# rgb-vfd-matrix.net
KiCad netlist of a schematic drawn in EAGLE
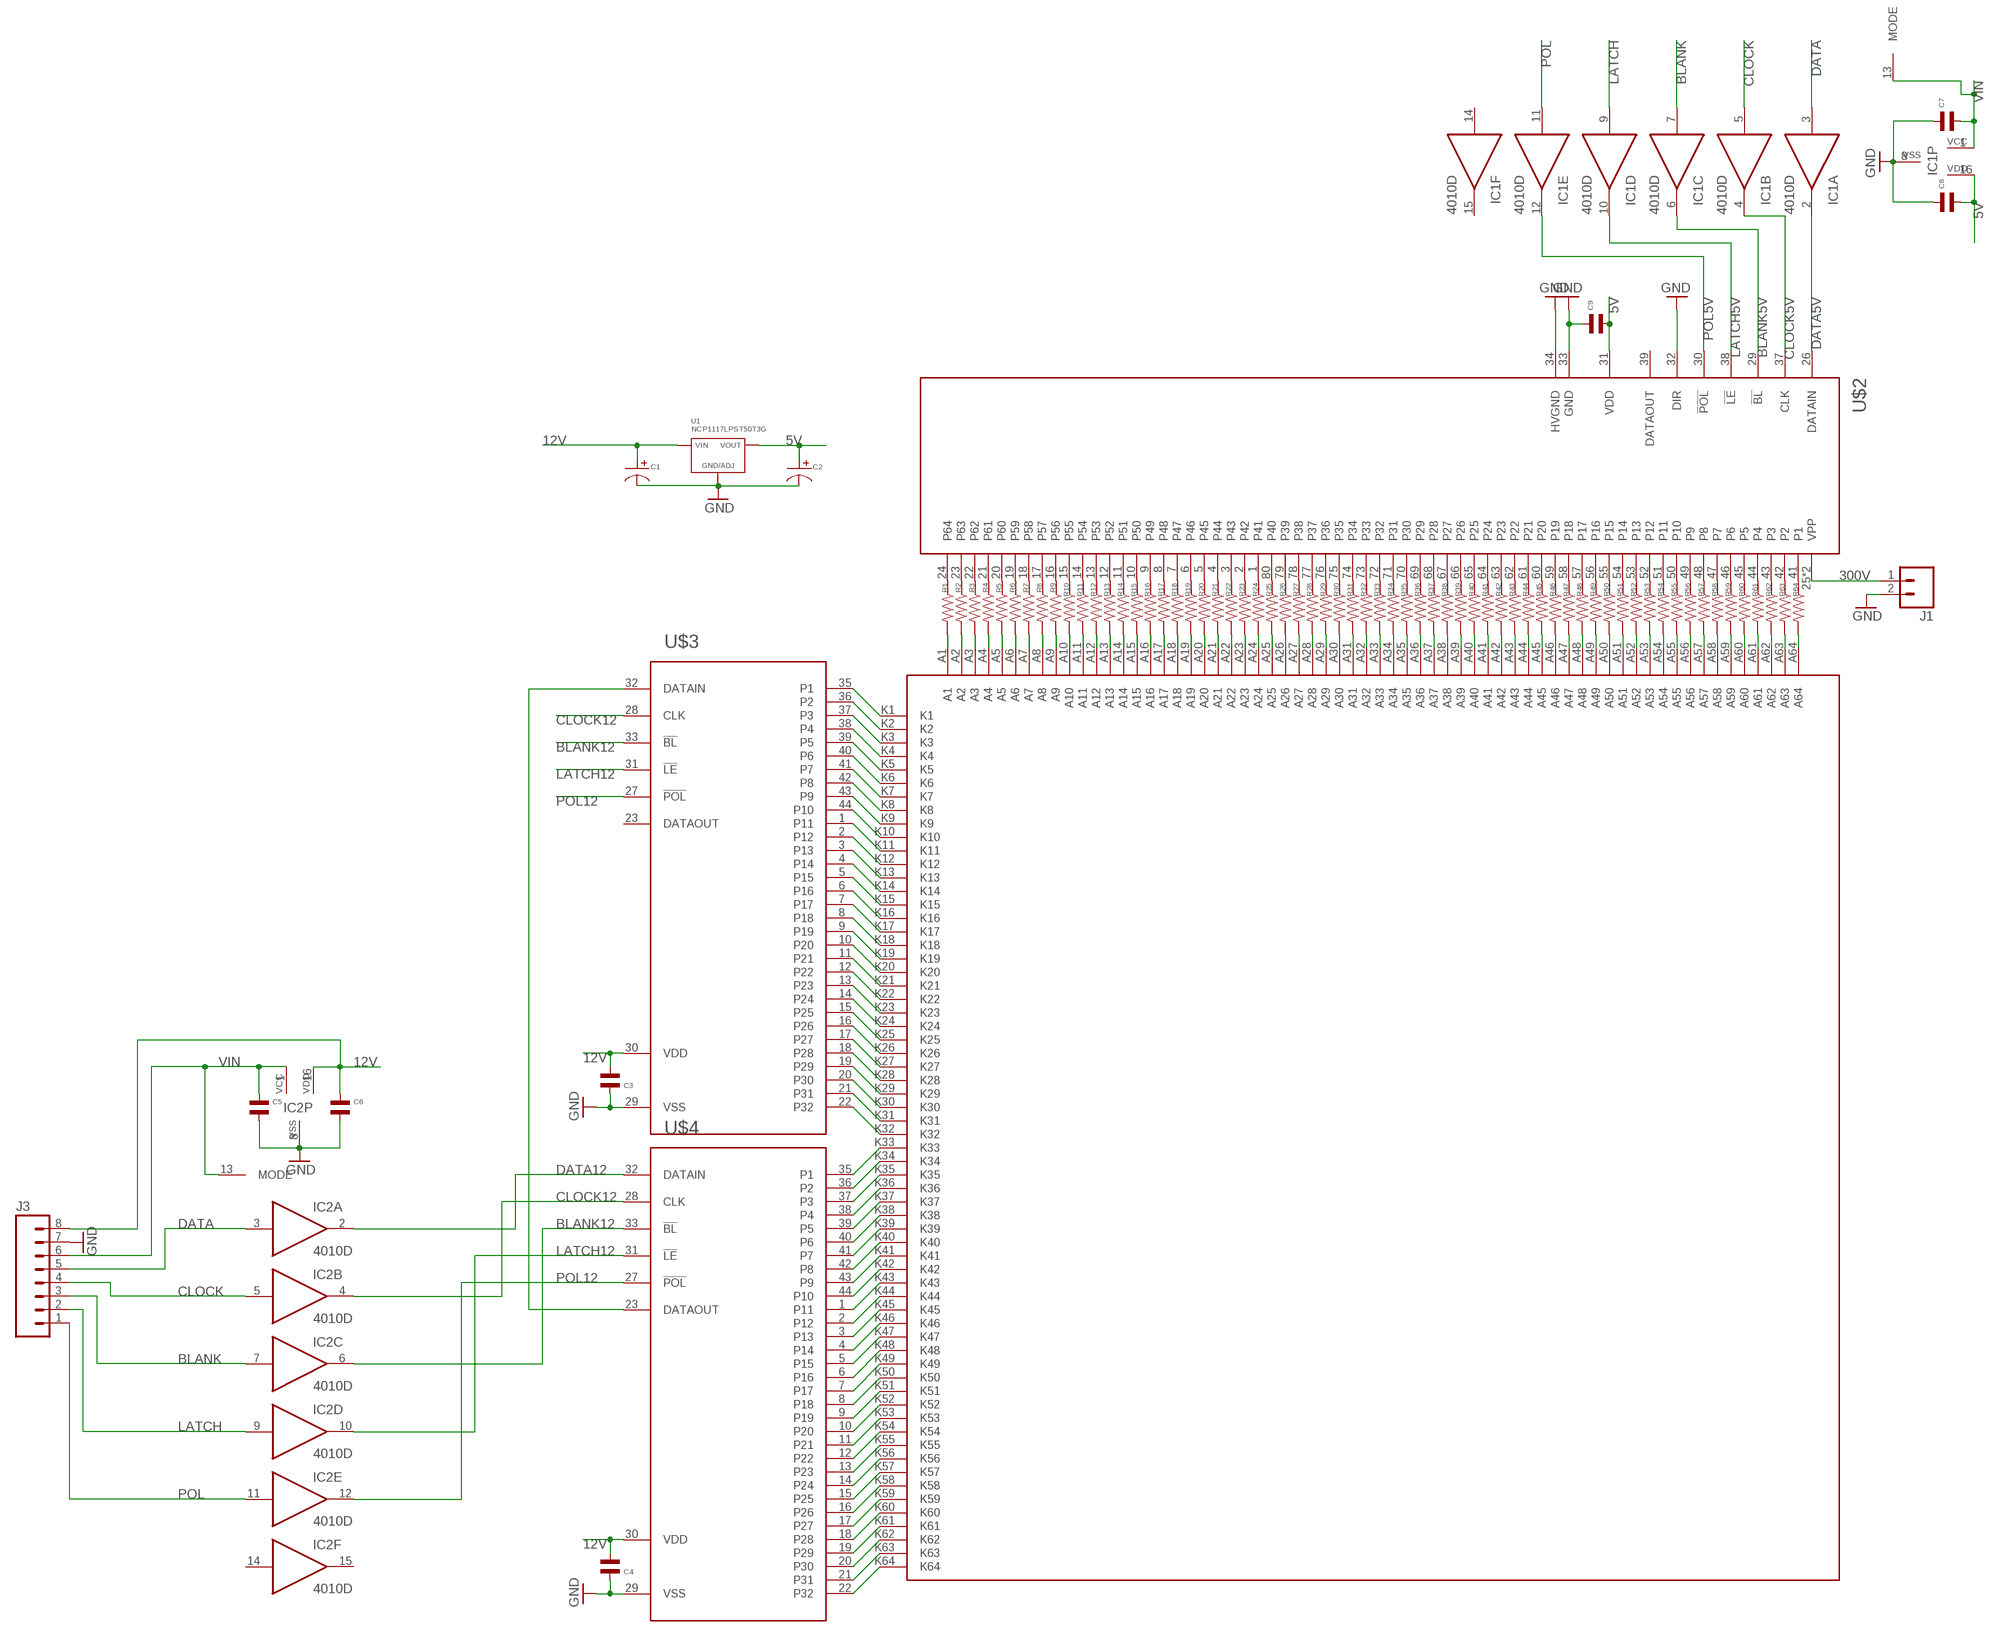
[diagram p0: schematic, sheet 1]

(export (version "E")
  (design (tool "Eeschema 10.0.6"))
  (components
    (comp (ref "C1")
      (value "CAPACITOR_P_8MM")
      (footprint "eagle-import:CP8MM")
      (libsource (lib "eagle-import") (part "CAPACITOR_P_8MM"))
    )
    (comp (ref "C2")
      (value "CAPACITOR_P_8MM")
      (footprint "eagle-import:CP8MM")
      (libsource (lib "eagle-import") (part "CAPACITOR_P_8MM"))
    )
    (comp (ref "C3")
      (value "CAPACITOR_NP_0603")
      (footprint "eagle-import:C0603")
      (libsource (lib "eagle-import") (part "CAPACITOR_NP_0603"))
    )
    (comp (ref "C4")
      (value "CAPACITOR_NP_0603")
      (footprint "eagle-import:C0603")
      (libsource (lib "eagle-import") (part "CAPACITOR_NP_0603"))
    )
    (comp (ref "C5")
      (value "CAPACITOR_NP_0603")
      (footprint "eagle-import:C0603")
      (libsource (lib "eagle-import") (part "CAPACITOR_NP_0603"))
    )
    (comp (ref "C6")
      (value "CAPACITOR_NP_0603")
      (footprint "eagle-import:C0603")
      (libsource (lib "eagle-import") (part "CAPACITOR_NP_0603"))
    )
    (comp (ref "C7")
      (value "CAPACITOR_NP_0603")
      (footprint "eagle-import:C0603")
      (libsource (lib "eagle-import") (part "CAPACITOR_NP_0603"))
    )
    (comp (ref "C8")
      (value "CAPACITOR_NP_0603")
      (footprint "eagle-import:C0603")
      (libsource (lib "eagle-import") (part "CAPACITOR_NP_0603"))
    )
    (comp (ref "C9")
      (value "CAPACITOR_NP_0603")
      (footprint "eagle-import:C0603")
      (libsource (lib "eagle-import") (part "CAPACITOR_NP_0603"))
    )
    (comp (ref "IC1")
      (value "4010D")
      (footprint "eagle-import:SO16")
      (libsource (lib "eagle-import") (part "4010D"))
    )
    (comp (ref "IC2")
      (value "4010D")
      (footprint "eagle-import:SO16")
      (libsource (lib "eagle-import") (part "4010D"))
    )
    (comp (ref "J1")
      (value "M023.5MM")
      (footprint "eagle-import:SCREWTERMINAL-3.5MM-2")
      (libsource (lib "eagle-import") (part "M023.5MM"))
    )
    (comp (ref "J3")
      (value "M083.5MM-8")
      (footprint "eagle-import:SCREWTERMINAL-3.5MM-8")
      (libsource (lib "eagle-import") (part "M083.5MM-8"))
    )
    (comp (ref "R1")
      (value "RESISTOR_0805")
      (footprint "eagle-import:R0805")
      (libsource (lib "eagle-import") (part "RESISTOR_0805"))
    )
    (comp (ref "R2")
      (value "RESISTOR_0805")
      (footprint "eagle-import:R0805")
      (libsource (lib "eagle-import") (part "RESISTOR_0805"))
    )
    (comp (ref "R3")
      (value "RESISTOR_0805")
      (footprint "eagle-import:R0805")
      (libsource (lib "eagle-import") (part "RESISTOR_0805"))
    )
    (comp (ref "R4")
      (value "RESISTOR_0805")
      (footprint "eagle-import:R0805")
      (libsource (lib "eagle-import") (part "RESISTOR_0805"))
    )
    (comp (ref "R5")
      (value "RESISTOR_0805")
      (footprint "eagle-import:R0805")
      (libsource (lib "eagle-import") (part "RESISTOR_0805"))
    )
    (comp (ref "R6")
      (value "RESISTOR_0805")
      (footprint "eagle-import:R0805")
      (libsource (lib "eagle-import") (part "RESISTOR_0805"))
    )
    (comp (ref "R7")
      (value "RESISTOR_0805")
      (footprint "eagle-import:R0805")
      (libsource (lib "eagle-import") (part "RESISTOR_0805"))
    )
    (comp (ref "R8")
      (value "RESISTOR_0805")
      (footprint "eagle-import:R0805")
      (libsource (lib "eagle-import") (part "RESISTOR_0805"))
    )
    (comp (ref "R9")
      (value "RESISTOR_0805")
      (footprint "eagle-import:R0805")
      (libsource (lib "eagle-import") (part "RESISTOR_0805"))
    )
    (comp (ref "R10")
      (value "RESISTOR_0805")
      (footprint "eagle-import:R0805")
      (libsource (lib "eagle-import") (part "RESISTOR_0805"))
    )
    (comp (ref "R11")
      (value "RESISTOR_0805")
      (footprint "eagle-import:R0805")
      (libsource (lib "eagle-import") (part "RESISTOR_0805"))
    )
    (comp (ref "R12")
      (value "RESISTOR_0805")
      (footprint "eagle-import:R0805")
      (libsource (lib "eagle-import") (part "RESISTOR_0805"))
    )
    (comp (ref "R13")
      (value "RESISTOR_0805")
      (footprint "eagle-import:R0805")
      (libsource (lib "eagle-import") (part "RESISTOR_0805"))
    )
    (comp (ref "R14")
      (value "RESISTOR_0805")
      (footprint "eagle-import:R0805")
      (libsource (lib "eagle-import") (part "RESISTOR_0805"))
    )
    (comp (ref "R15")
      (value "RESISTOR_0805")
      (footprint "eagle-import:R0805")
      (libsource (lib "eagle-import") (part "RESISTOR_0805"))
    )
    (comp (ref "R16")
      (value "RESISTOR_0805")
      (footprint "eagle-import:R0805")
      (libsource (lib "eagle-import") (part "RESISTOR_0805"))
    )
    (comp (ref "R17")
      (value "RESISTOR_0805")
      (footprint "eagle-import:R0805")
      (libsource (lib "eagle-import") (part "RESISTOR_0805"))
    )
    (comp (ref "R18")
      (value "RESISTOR_0805")
      (footprint "eagle-import:R0805")
      (libsource (lib "eagle-import") (part "RESISTOR_0805"))
    )
    (comp (ref "R19")
      (value "RESISTOR_0805")
      (footprint "eagle-import:R0805")
      (libsource (lib "eagle-import") (part "RESISTOR_0805"))
    )
    (comp (ref "R20")
      (value "RESISTOR_0805")
      (footprint "eagle-import:R0805")
      (libsource (lib "eagle-import") (part "RESISTOR_0805"))
    )
    (comp (ref "R21")
      (value "RESISTOR_0805")
      (footprint "eagle-import:R0805")
      (libsource (lib "eagle-import") (part "RESISTOR_0805"))
    )
    (comp (ref "R22")
      (value "RESISTOR_0805")
      (footprint "eagle-import:R0805")
      (libsource (lib "eagle-import") (part "RESISTOR_0805"))
    )
    (comp (ref "R23")
      (value "RESISTOR_0805")
      (footprint "eagle-import:R0805")
      (libsource (lib "eagle-import") (part "RESISTOR_0805"))
    )
    (comp (ref "R24")
      (value "RESISTOR_0805")
      (footprint "eagle-import:R0805")
      (libsource (lib "eagle-import") (part "RESISTOR_0805"))
    )
    (comp (ref "R25")
      (value "RESISTOR_0805")
      (footprint "eagle-import:R0805")
      (libsource (lib "eagle-import") (part "RESISTOR_0805"))
    )
    (comp (ref "R26")
      (value "RESISTOR_0805")
      (footprint "eagle-import:R0805")
      (libsource (lib "eagle-import") (part "RESISTOR_0805"))
    )
    (comp (ref "R27")
      (value "RESISTOR_0805")
      (footprint "eagle-import:R0805")
      (libsource (lib "eagle-import") (part "RESISTOR_0805"))
    )
    (comp (ref "R28")
      (value "RESISTOR_0805")
      (footprint "eagle-import:R0805")
      (libsource (lib "eagle-import") (part "RESISTOR_0805"))
    )
    (comp (ref "R29")
      (value "RESISTOR_0805")
      (footprint "eagle-import:R0805")
      (libsource (lib "eagle-import") (part "RESISTOR_0805"))
    )
    (comp (ref "R30")
      (value "RESISTOR_0805")
      (footprint "eagle-import:R0805")
      (libsource (lib "eagle-import") (part "RESISTOR_0805"))
    )
    (comp (ref "R31")
      (value "RESISTOR_0805")
      (footprint "eagle-import:R0805")
      (libsource (lib "eagle-import") (part "RESISTOR_0805"))
    )
    (comp (ref "R32")
      (value "RESISTOR_0805")
      (footprint "eagle-import:R0805")
      (libsource (lib "eagle-import") (part "RESISTOR_0805"))
    )
    (comp (ref "R33")
      (value "RESISTOR_0805")
      (footprint "eagle-import:R0805")
      (libsource (lib "eagle-import") (part "RESISTOR_0805"))
    )
    (comp (ref "R34")
      (value "RESISTOR_0805")
      (footprint "eagle-import:R0805")
      (libsource (lib "eagle-import") (part "RESISTOR_0805"))
    )
    (comp (ref "R35")
      (value "RESISTOR_0805")
      (footprint "eagle-import:R0805")
      (libsource (lib "eagle-import") (part "RESISTOR_0805"))
    )
    (comp (ref "R36")
      (value "RESISTOR_0805")
      (footprint "eagle-import:R0805")
      (libsource (lib "eagle-import") (part "RESISTOR_0805"))
    )
    (comp (ref "R37")
      (value "RESISTOR_0805")
      (footprint "eagle-import:R0805")
      (libsource (lib "eagle-import") (part "RESISTOR_0805"))
    )
    (comp (ref "R38")
      (value "RESISTOR_0805")
      (footprint "eagle-import:R0805")
      (libsource (lib "eagle-import") (part "RESISTOR_0805"))
    )
    (comp (ref "R39")
      (value "RESISTOR_0805")
      (footprint "eagle-import:R0805")
      (libsource (lib "eagle-import") (part "RESISTOR_0805"))
    )
    (comp (ref "R40")
      (value "RESISTOR_0805")
      (footprint "eagle-import:R0805")
      (libsource (lib "eagle-import") (part "RESISTOR_0805"))
    )
    (comp (ref "R41")
      (value "RESISTOR_0805")
      (footprint "eagle-import:R0805")
      (libsource (lib "eagle-import") (part "RESISTOR_0805"))
    )
    (comp (ref "R42")
      (value "RESISTOR_0805")
      (footprint "eagle-import:R0805")
      (libsource (lib "eagle-import") (part "RESISTOR_0805"))
    )
    (comp (ref "R43")
      (value "RESISTOR_0805")
      (footprint "eagle-import:R0805")
      (libsource (lib "eagle-import") (part "RESISTOR_0805"))
    )
    (comp (ref "R44")
      (value "RESISTOR_0805")
      (footprint "eagle-import:R0805")
      (libsource (lib "eagle-import") (part "RESISTOR_0805"))
    )
    (comp (ref "R45")
      (value "RESISTOR_0805")
      (footprint "eagle-import:R0805")
      (libsource (lib "eagle-import") (part "RESISTOR_0805"))
    )
    (comp (ref "R46")
      (value "RESISTOR_0805")
      (footprint "eagle-import:R0805")
      (libsource (lib "eagle-import") (part "RESISTOR_0805"))
    )
    (comp (ref "R47")
      (value "RESISTOR_0805")
      (footprint "eagle-import:R0805")
      (libsource (lib "eagle-import") (part "RESISTOR_0805"))
    )
    (comp (ref "R48")
      (value "RESISTOR_0805")
      (footprint "eagle-import:R0805")
      (libsource (lib "eagle-import") (part "RESISTOR_0805"))
    )
    (comp (ref "R49")
      (value "RESISTOR_0805")
      (footprint "eagle-import:R0805")
      (libsource (lib "eagle-import") (part "RESISTOR_0805"))
    )
    (comp (ref "R50")
      (value "RESISTOR_0805")
      (footprint "eagle-import:R0805")
      (libsource (lib "eagle-import") (part "RESISTOR_0805"))
    )
    (comp (ref "R51")
      (value "RESISTOR_0805")
      (footprint "eagle-import:R0805")
      (libsource (lib "eagle-import") (part "RESISTOR_0805"))
    )
    (comp (ref "R52")
      (value "RESISTOR_0805")
      (footprint "eagle-import:R0805")
      (libsource (lib "eagle-import") (part "RESISTOR_0805"))
    )
    (comp (ref "R53")
      (value "RESISTOR_0805")
      (footprint "eagle-import:R0805")
      (libsource (lib "eagle-import") (part "RESISTOR_0805"))
    )
    (comp (ref "R54")
      (value "RESISTOR_0805")
      (footprint "eagle-import:R0805")
      (libsource (lib "eagle-import") (part "RESISTOR_0805"))
    )
    (comp (ref "R55")
      (value "RESISTOR_0805")
      (footprint "eagle-import:R0805")
      (libsource (lib "eagle-import") (part "RESISTOR_0805"))
    )
    (comp (ref "R56")
      (value "RESISTOR_0805")
      (footprint "eagle-import:R0805")
      (libsource (lib "eagle-import") (part "RESISTOR_0805"))
    )
    (comp (ref "R57")
      (value "RESISTOR_0805")
      (footprint "eagle-import:R0805")
      (libsource (lib "eagle-import") (part "RESISTOR_0805"))
    )
    (comp (ref "R58")
      (value "RESISTOR_0805")
      (footprint "eagle-import:R0805")
      (libsource (lib "eagle-import") (part "RESISTOR_0805"))
    )
    (comp (ref "R59")
      (value "RESISTOR_0805")
      (footprint "eagle-import:R0805")
      (libsource (lib "eagle-import") (part "RESISTOR_0805"))
    )
    (comp (ref "R60")
      (value "RESISTOR_0805")
      (footprint "eagle-import:R0805")
      (libsource (lib "eagle-import") (part "RESISTOR_0805"))
    )
    (comp (ref "R61")
      (value "RESISTOR_0805")
      (footprint "eagle-import:R0805")
      (libsource (lib "eagle-import") (part "RESISTOR_0805"))
    )
    (comp (ref "R62")
      (value "RESISTOR_0805")
      (footprint "eagle-import:R0805")
      (libsource (lib "eagle-import") (part "RESISTOR_0805"))
    )
    (comp (ref "R63")
      (value "RESISTOR_0805")
      (footprint "eagle-import:R0805")
      (libsource (lib "eagle-import") (part "RESISTOR_0805"))
    )
    (comp (ref "R64")
      (value "RESISTOR_0805")
      (footprint "eagle-import:R0805")
      (libsource (lib "eagle-import") (part "RESISTOR_0805"))
    )
    (comp (ref "U$1")
      (value "RGBVFDMATRIX")
      (footprint "eagle-import:RGBVFDMATRIX")
      (libsource (lib "eagle-import") (part "RGBVFDMATRIX"))
    )
    (comp (ref "U$2")
      (value "HV507")
      (footprint "eagle-import:PQFP80")
      (libsource (lib "eagle-import") (part "HV507"))
    )
    (comp (ref "U$3")
      (value "HV5530")
      (footprint "eagle-import:PQFP44")
      (libsource (lib "eagle-import") (part "HV5530"))
    )
    (comp (ref "U$4")
      (value "HV5530")
      (footprint "eagle-import:PQFP44")
      (libsource (lib "eagle-import") (part "HV5530"))
    )
    (comp (ref "U1")
      (value "NCP1117LPST50T3G")
      (footprint "eagle-import:SOT-223-3")
      (fields (field (name "HOUSEPART") "NO"))
      (libsource (lib "eagle-import") (part "NCP1117LPST50T3G"))
    )
  )
  (nets
    (net (code "1") (name "/5V") (class "Default")
      (node (ref "C2") (pin "P$1") (pinfunction "P$1_P$1") (pintype "passive"))
      (node (ref "C8") (pin "P$2") (pinfunction "P$2_P$2") (pintype "passive"))
      (node (ref "C9") (pin "P$2") (pinfunction "P$2_P$2") (pintype "passive"))
      (node (ref "IC1") (pin "16") (pinfunction "VDD_16") (pintype "power_in"))
      (node (ref "U$2") (pin "31") (pinfunction "VDD_31") (pintype "bidirectional"))
      (node (ref "U1") (pin "P$1") (pinfunction "VOUT_P$1") (pintype "bidirectional"))
      (node (ref "U1") (pin "P$3") (pinfunction "VOUT_P$3") (pintype "bidirectional"))
    )
    (net (code "2") (name "/12V") (class "Default")
      (node (ref "C1") (pin "P$1") (pinfunction "P$1_P$1") (pintype "passive"))
      (node (ref "C3") (pin "P$2") (pinfunction "P$2_P$2") (pintype "passive"))
      (node (ref "C4") (pin "P$2") (pinfunction "P$2_P$2") (pintype "passive"))
      (node (ref "C6") (pin "P$1") (pinfunction "P$1_P$1") (pintype "passive"))
      (node (ref "IC2") (pin "16") (pinfunction "VDD_16") (pintype "power_in"))
      (node (ref "J3") (pin "8") (pinfunction "8_8") (pintype "passive"))
      (node (ref "U$3") (pin "30") (pinfunction "VDD_30") (pintype "bidirectional"))
      (node (ref "U$4") (pin "30") (pinfunction "VDD_30") (pintype "bidirectional"))
      (node (ref "U1") (pin "P$4") (pinfunction "VIN_P$4") (pintype "bidirectional"))
    )
    (net (code "3") (name "/300V") (class "Default")
      (node (ref "J1") (pin "1") (pinfunction "1_1") (pintype "passive"))
      (node (ref "U$2") (pin "25") (pinfunction "VPP_25") (pintype "bidirectional"))
      (node (ref "U$2") (pin "40") (pinfunction "VPP_40") (pintype "bidirectional"))
    )
    (net (code "4") (name "/BLANK") (class "Default")
      (node (ref "IC1") (pin "7") (pinfunction "I_7") (pintype "input"))
      (node (ref "IC2") (pin "7") (pinfunction "I_7") (pintype "input"))
      (node (ref "J3") (pin "3") (pinfunction "3_3") (pintype "passive"))
    )
    (net (code "5") (name "/BLANK5V") (class "Default")
      (node (ref "IC1") (pin "6") (pinfunction "O_6") (pintype "output"))
      (node (ref "U$2") (pin "29") (pinfunction "~{BL}_29") (pintype "bidirectional"))
    )
    (net (code "6") (name "/BLANK12") (class "Default")
      (node (ref "IC2") (pin "6") (pinfunction "O_6") (pintype "output"))
      (node (ref "U$3") (pin "33") (pinfunction "~{BL}_33") (pintype "bidirectional"))
      (node (ref "U$4") (pin "33") (pinfunction "~{BL}_33") (pintype "bidirectional"))
    )
    (net (code "7") (name "/CLOCK") (class "Default")
      (node (ref "IC1") (pin "5") (pinfunction "I_5") (pintype "input"))
      (node (ref "IC2") (pin "5") (pinfunction "I_5") (pintype "input"))
      (node (ref "J3") (pin "4") (pinfunction "4_4") (pintype "passive"))
    )
    (net (code "8") (name "/CLOCK5V") (class "Default")
      (node (ref "IC1") (pin "4") (pinfunction "O_4") (pintype "output"))
      (node (ref "U$2") (pin "37") (pinfunction "CLK_37") (pintype "bidirectional"))
    )
    (net (code "9") (name "/CLOCK12") (class "Default")
      (node (ref "IC2") (pin "4") (pinfunction "O_4") (pintype "output"))
      (node (ref "U$3") (pin "28") (pinfunction "CLK_28") (pintype "bidirectional"))
      (node (ref "U$4") (pin "28") (pinfunction "CLK_28") (pintype "bidirectional"))
    )
    (net (code "10") (name "/DATA") (class "Default")
      (node (ref "IC1") (pin "3") (pinfunction "I_3") (pintype "input"))
      (node (ref "IC2") (pin "3") (pinfunction "I_3") (pintype "input"))
      (node (ref "J3") (pin "5") (pinfunction "5_5") (pintype "passive"))
    )
    (net (code "11") (name "/DATA5V") (class "Default")
      (node (ref "IC1") (pin "2") (pinfunction "O_2") (pintype "output"))
      (node (ref "U$2") (pin "26") (pinfunction "DATAIN_26") (pintype "bidirectional"))
    )
    (net (code "12") (name "/DATA12") (class "Default")
      (node (ref "IC2") (pin "2") (pinfunction "O_2") (pintype "output"))
      (node (ref "U$4") (pin "32") (pinfunction "DATAIN_32") (pintype "bidirectional"))
    )
    (net (code "13") (name "/LATCH") (class "Default")
      (node (ref "IC1") (pin "9") (pinfunction "I_9") (pintype "input"))
      (node (ref "IC2") (pin "9") (pinfunction "I_9") (pintype "input"))
      (node (ref "J3") (pin "2") (pinfunction "2_2") (pintype "passive"))
    )
    (net (code "14") (name "/LATCH5V") (class "Default")
      (node (ref "IC1") (pin "10") (pinfunction "O_10") (pintype "output"))
      (node (ref "U$2") (pin "38") (pinfunction "~{LE}_38") (pintype "bidirectional"))
    )
    (net (code "15") (name "/LATCH12") (class "Default")
      (node (ref "IC2") (pin "10") (pinfunction "O_10") (pintype "output"))
      (node (ref "U$3") (pin "31") (pinfunction "~{LE}_31") (pintype "bidirectional"))
      (node (ref "U$4") (pin "31") (pinfunction "~{LE}_31") (pintype "bidirectional"))
    )
    (net (code "16") (name "/POL") (class "Default")
      (node (ref "IC1") (pin "11") (pinfunction "I_11") (pintype "input"))
      (node (ref "IC2") (pin "11") (pinfunction "I_11") (pintype "input"))
      (node (ref "J3") (pin "1") (pinfunction "1_1") (pintype "passive"))
    )
    (net (code "17") (name "/POL5V") (class "Default")
      (node (ref "IC1") (pin "12") (pinfunction "O_12") (pintype "output"))
      (node (ref "U$2") (pin "30") (pinfunction "~{POL}_30") (pintype "bidirectional"))
    )
    (net (code "18") (name "/POL12") (class "Default")
      (node (ref "IC2") (pin "12") (pinfunction "O_12") (pintype "output"))
      (node (ref "U$3") (pin "27") (pinfunction "~{POL}_27") (pintype "bidirectional"))
      (node (ref "U$4") (pin "27") (pinfunction "~{POL}_27") (pintype "bidirectional"))
    )
    (net (code "19") (name "/VIN") (class "Default")
      (node (ref "C5") (pin "P$1") (pinfunction "P$1_P$1") (pintype "passive"))
      (node (ref "C7") (pin "P$2") (pinfunction "P$2_P$2") (pintype "passive"))
      (node (ref "IC1") (pin "1") (pinfunction "VCC_1") (pintype "power_in"))
      (node (ref "IC1") (pin "13") (pinfunction "MODE_13") (pintype "bidirectional"))
      (node (ref "IC2") (pin "1") (pinfunction "VCC_1") (pintype "power_in"))
      (node (ref "IC2") (pin "13") (pinfunction "MODE_13") (pintype "bidirectional"))
      (node (ref "J3") (pin "6") (pinfunction "6_6") (pintype "passive"))
    )
    (net (code "20") (name "GND") (class "Default")
      (node (ref "C1") (pin "P$2") (pinfunction "P$2_P$2") (pintype "passive"))
      (node (ref "C2") (pin "P$2") (pinfunction "P$2_P$2") (pintype "passive"))
      (node (ref "C3") (pin "P$1") (pinfunction "P$1_P$1") (pintype "passive"))
      (node (ref "C4") (pin "P$1") (pinfunction "P$1_P$1") (pintype "passive"))
      (node (ref "C5") (pin "P$2") (pinfunction "P$2_P$2") (pintype "passive"))
      (node (ref "C6") (pin "P$2") (pinfunction "P$2_P$2") (pintype "passive"))
      (node (ref "C7") (pin "P$1") (pinfunction "P$1_P$1") (pintype "passive"))
      (node (ref "C8") (pin "P$1") (pinfunction "P$1_P$1") (pintype "passive"))
      (node (ref "C9") (pin "P$1") (pinfunction "P$1_P$1") (pintype "passive"))
      (node (ref "IC1") (pin "8") (pinfunction "VSS_8") (pintype "power_in"))
      (node (ref "IC2") (pin "8") (pinfunction "VSS_8") (pintype "power_in"))
      (node (ref "J1") (pin "2") (pinfunction "2_2") (pintype "passive"))
      (node (ref "J3") (pin "7") (pinfunction "7_7") (pintype "passive"))
      (node (ref "U$2") (pin "32") (pinfunction "DIR_32") (pintype "bidirectional"))
      (node (ref "U$2") (pin "33") (pinfunction "GND_33") (pintype "bidirectional"))
      (node (ref "U$2") (pin "34") (pinfunction "HVGND_34") (pintype "bidirectional"))
      (node (ref "U$3") (pin "29") (pinfunction "VSS_29") (pintype "bidirectional"))
      (node (ref "U$4") (pin "29") (pinfunction "VSS_29") (pintype "bidirectional"))
      (node (ref "U1") (pin "P$2") (pinfunction "GND/ADJ_P$2") (pintype "bidirectional"))
    )
    (net (code "21") (name "Net-(R1-PadP$2)") (class "Default")
      (node (ref "R1") (pin "P$2") (pinfunction "P$2_P$2") (pintype "passive"))
      (node (ref "U$1") (pin "A1") (pinfunction "A1_A1") (pintype "bidirectional"))
    )
    (net (code "22") (name "Net-(R2-PadP$2)") (class "Default")
      (node (ref "R2") (pin "P$2") (pinfunction "P$2_P$2") (pintype "passive"))
      (node (ref "U$1") (pin "A2") (pinfunction "A2_A2") (pintype "bidirectional"))
    )
    (net (code "23") (name "Net-(R3-PadP$2)") (class "Default")
      (node (ref "R3") (pin "P$2") (pinfunction "P$2_P$2") (pintype "passive"))
      (node (ref "U$1") (pin "A3") (pinfunction "A3_A3") (pintype "bidirectional"))
    )
    (net (code "24") (name "Net-(R4-PadP$2)") (class "Default")
      (node (ref "R4") (pin "P$2") (pinfunction "P$2_P$2") (pintype "passive"))
      (node (ref "U$1") (pin "A4") (pinfunction "A4_A4") (pintype "bidirectional"))
    )
    (net (code "25") (name "Net-(R5-PadP$2)") (class "Default")
      (node (ref "R5") (pin "P$2") (pinfunction "P$2_P$2") (pintype "passive"))
      (node (ref "U$1") (pin "A5") (pinfunction "A5_A5") (pintype "bidirectional"))
    )
    (net (code "26") (name "Net-(R6-PadP$2)") (class "Default")
      (node (ref "R6") (pin "P$2") (pinfunction "P$2_P$2") (pintype "passive"))
      (node (ref "U$1") (pin "A6") (pinfunction "A6_A6") (pintype "bidirectional"))
    )
    (net (code "27") (name "Net-(R7-PadP$2)") (class "Default")
      (node (ref "R7") (pin "P$2") (pinfunction "P$2_P$2") (pintype "passive"))
      (node (ref "U$1") (pin "A7") (pinfunction "A7_A7") (pintype "bidirectional"))
    )
    (net (code "28") (name "Net-(R8-PadP$2)") (class "Default")
      (node (ref "R8") (pin "P$2") (pinfunction "P$2_P$2") (pintype "passive"))
      (node (ref "U$1") (pin "A8") (pinfunction "A8_A8") (pintype "bidirectional"))
    )
    (net (code "29") (name "Net-(R9-PadP$2)") (class "Default")
      (node (ref "R9") (pin "P$2") (pinfunction "P$2_P$2") (pintype "passive"))
      (node (ref "U$1") (pin "A9") (pinfunction "A9_A9") (pintype "bidirectional"))
    )
    (net (code "30") (name "Net-(R10-PadP$2)") (class "Default")
      (node (ref "R10") (pin "P$2") (pinfunction "P$2_P$2") (pintype "passive"))
      (node (ref "U$1") (pin "A10") (pinfunction "A10_A10") (pintype "bidirectional"))
    )
    (net (code "31") (name "Net-(R11-PadP$2)") (class "Default")
      (node (ref "R11") (pin "P$2") (pinfunction "P$2_P$2") (pintype "passive"))
      (node (ref "U$1") (pin "A11") (pinfunction "A11_A11") (pintype "bidirectional"))
    )
    (net (code "32") (name "Net-(R12-PadP$2)") (class "Default")
      (node (ref "R12") (pin "P$2") (pinfunction "P$2_P$2") (pintype "passive"))
      (node (ref "U$1") (pin "A12") (pinfunction "A12_A12") (pintype "bidirectional"))
    )
    (net (code "33") (name "Net-(R13-PadP$2)") (class "Default")
      (node (ref "R13") (pin "P$2") (pinfunction "P$2_P$2") (pintype "passive"))
      (node (ref "U$1") (pin "A13") (pinfunction "A13_A13") (pintype "bidirectional"))
    )
    (net (code "34") (name "Net-(R14-PadP$2)") (class "Default")
      (node (ref "R14") (pin "P$2") (pinfunction "P$2_P$2") (pintype "passive"))
      (node (ref "U$1") (pin "A14") (pinfunction "A14_A14") (pintype "bidirectional"))
    )
    (net (code "35") (name "Net-(R15-PadP$2)") (class "Default")
      (node (ref "R15") (pin "P$2") (pinfunction "P$2_P$2") (pintype "passive"))
      (node (ref "U$1") (pin "A15") (pinfunction "A15_A15") (pintype "bidirectional"))
    )
    (net (code "36") (name "Net-(R16-PadP$2)") (class "Default")
      (node (ref "R16") (pin "P$2") (pinfunction "P$2_P$2") (pintype "passive"))
      (node (ref "U$1") (pin "A16") (pinfunction "A16_A16") (pintype "bidirectional"))
    )
    (net (code "37") (name "Net-(R17-PadP$2)") (class "Default")
      (node (ref "R17") (pin "P$2") (pinfunction "P$2_P$2") (pintype "passive"))
      (node (ref "U$1") (pin "A17") (pinfunction "A17_A17") (pintype "bidirectional"))
    )
    (net (code "38") (name "Net-(R18-PadP$2)") (class "Default")
      (node (ref "R18") (pin "P$2") (pinfunction "P$2_P$2") (pintype "passive"))
      (node (ref "U$1") (pin "A18") (pinfunction "A18_A18") (pintype "bidirectional"))
    )
    (net (code "39") (name "Net-(R19-PadP$2)") (class "Default")
      (node (ref "R19") (pin "P$2") (pinfunction "P$2_P$2") (pintype "passive"))
      (node (ref "U$1") (pin "A19") (pinfunction "A19_A19") (pintype "bidirectional"))
    )
    (net (code "40") (name "Net-(R20-PadP$2)") (class "Default")
      (node (ref "R20") (pin "P$2") (pinfunction "P$2_P$2") (pintype "passive"))
      (node (ref "U$1") (pin "A20") (pinfunction "A20_A20") (pintype "bidirectional"))
    )
    (net (code "41") (name "Net-(R21-PadP$2)") (class "Default")
      (node (ref "R21") (pin "P$2") (pinfunction "P$2_P$2") (pintype "passive"))
      (node (ref "U$1") (pin "A21") (pinfunction "A21_A21") (pintype "bidirectional"))
    )
    (net (code "42") (name "Net-(R22-PadP$2)") (class "Default")
      (node (ref "R22") (pin "P$2") (pinfunction "P$2_P$2") (pintype "passive"))
      (node (ref "U$1") (pin "A22") (pinfunction "A22_A22") (pintype "bidirectional"))
    )
    (net (code "43") (name "Net-(R23-PadP$2)") (class "Default")
      (node (ref "R23") (pin "P$2") (pinfunction "P$2_P$2") (pintype "passive"))
      (node (ref "U$1") (pin "A23") (pinfunction "A23_A23") (pintype "bidirectional"))
    )
    (net (code "44") (name "Net-(R24-PadP$2)") (class "Default")
      (node (ref "R24") (pin "P$2") (pinfunction "P$2_P$2") (pintype "passive"))
      (node (ref "U$1") (pin "A24") (pinfunction "A24_A24") (pintype "bidirectional"))
    )
    (net (code "45") (name "Net-(R25-PadP$2)") (class "Default")
      (node (ref "R25") (pin "P$2") (pinfunction "P$2_P$2") (pintype "passive"))
      (node (ref "U$1") (pin "A25") (pinfunction "A25_A25") (pintype "bidirectional"))
    )
    (net (code "46") (name "Net-(R26-PadP$2)") (class "Default")
      (node (ref "R26") (pin "P$2") (pinfunction "P$2_P$2") (pintype "passive"))
      (node (ref "U$1") (pin "A26") (pinfunction "A26_A26") (pintype "bidirectional"))
    )
    (net (code "47") (name "Net-(R27-PadP$2)") (class "Default")
      (node (ref "R27") (pin "P$2") (pinfunction "P$2_P$2") (pintype "passive"))
      (node (ref "U$1") (pin "A27") (pinfunction "A27_A27") (pintype "bidirectional"))
    )
    (net (code "48") (name "Net-(R28-PadP$2)") (class "Default")
      (node (ref "R28") (pin "P$2") (pinfunction "P$2_P$2") (pintype "passive"))
      (node (ref "U$1") (pin "A28") (pinfunction "A28_A28") (pintype "bidirectional"))
    )
    (net (code "49") (name "Net-(R29-PadP$2)") (class "Default")
      (node (ref "R29") (pin "P$2") (pinfunction "P$2_P$2") (pintype "passive"))
      (node (ref "U$1") (pin "A29") (pinfunction "A29_A29") (pintype "bidirectional"))
    )
    (net (code "50") (name "Net-(R30-PadP$2)") (class "Default")
      (node (ref "R30") (pin "P$2") (pinfunction "P$2_P$2") (pintype "passive"))
      (node (ref "U$1") (pin "A30") (pinfunction "A30_A30") (pintype "bidirectional"))
    )
    (net (code "51") (name "Net-(R31-PadP$2)") (class "Default")
      (node (ref "R31") (pin "P$2") (pinfunction "P$2_P$2") (pintype "passive"))
      (node (ref "U$1") (pin "A31") (pinfunction "A31_A31") (pintype "bidirectional"))
    )
    (net (code "52") (name "Net-(R32-PadP$2)") (class "Default")
      (node (ref "R32") (pin "P$2") (pinfunction "P$2_P$2") (pintype "passive"))
      (node (ref "U$1") (pin "A32") (pinfunction "A32_A32") (pintype "bidirectional"))
    )
    (net (code "53") (name "Net-(R33-PadP$2)") (class "Default")
      (node (ref "R33") (pin "P$2") (pinfunction "P$2_P$2") (pintype "passive"))
      (node (ref "U$1") (pin "A33") (pinfunction "A33_A33") (pintype "bidirectional"))
    )
    (net (code "54") (name "Net-(R34-PadP$2)") (class "Default")
      (node (ref "R34") (pin "P$2") (pinfunction "P$2_P$2") (pintype "passive"))
      (node (ref "U$1") (pin "A34") (pinfunction "A34_A34") (pintype "bidirectional"))
    )
    (net (code "55") (name "Net-(R35-PadP$2)") (class "Default")
      (node (ref "R35") (pin "P$2") (pinfunction "P$2_P$2") (pintype "passive"))
      (node (ref "U$1") (pin "A35") (pinfunction "A35_A35") (pintype "bidirectional"))
    )
    (net (code "56") (name "Net-(R36-PadP$2)") (class "Default")
      (node (ref "R36") (pin "P$2") (pinfunction "P$2_P$2") (pintype "passive"))
      (node (ref "U$1") (pin "A36") (pinfunction "A36_A36") (pintype "bidirectional"))
    )
    (net (code "57") (name "Net-(R37-PadP$2)") (class "Default")
      (node (ref "R37") (pin "P$2") (pinfunction "P$2_P$2") (pintype "passive"))
      (node (ref "U$1") (pin "A37") (pinfunction "A37_A37") (pintype "bidirectional"))
    )
    (net (code "58") (name "Net-(R38-PadP$2)") (class "Default")
      (node (ref "R38") (pin "P$2") (pinfunction "P$2_P$2") (pintype "passive"))
      (node (ref "U$1") (pin "A38") (pinfunction "A38_A38") (pintype "bidirectional"))
    )
    (net (code "59") (name "Net-(R39-PadP$2)") (class "Default")
      (node (ref "R39") (pin "P$2") (pinfunction "P$2_P$2") (pintype "passive"))
      (node (ref "U$1") (pin "A39") (pinfunction "A39_A39") (pintype "bidirectional"))
    )
    (net (code "60") (name "Net-(R40-PadP$2)") (class "Default")
      (node (ref "R40") (pin "P$2") (pinfunction "P$2_P$2") (pintype "passive"))
      (node (ref "U$1") (pin "A40") (pinfunction "A40_A40") (pintype "bidirectional"))
    )
    (net (code "61") (name "Net-(R41-PadP$2)") (class "Default")
      (node (ref "R41") (pin "P$2") (pinfunction "P$2_P$2") (pintype "passive"))
      (node (ref "U$1") (pin "A41") (pinfunction "A41_A41") (pintype "bidirectional"))
    )
    (net (code "62") (name "Net-(R42-PadP$2)") (class "Default")
      (node (ref "R42") (pin "P$2") (pinfunction "P$2_P$2") (pintype "passive"))
      (node (ref "U$1") (pin "A42") (pinfunction "A42_A42") (pintype "bidirectional"))
    )
    (net (code "63") (name "Net-(R43-PadP$2)") (class "Default")
      (node (ref "R43") (pin "P$2") (pinfunction "P$2_P$2") (pintype "passive"))
      (node (ref "U$1") (pin "A43") (pinfunction "A43_A43") (pintype "bidirectional"))
    )
    (net (code "64") (name "Net-(R44-PadP$2)") (class "Default")
      (node (ref "R44") (pin "P$2") (pinfunction "P$2_P$2") (pintype "passive"))
      (node (ref "U$1") (pin "A44") (pinfunction "A44_A44") (pintype "bidirectional"))
    )
    (net (code "65") (name "Net-(R45-PadP$2)") (class "Default")
      (node (ref "R45") (pin "P$2") (pinfunction "P$2_P$2") (pintype "passive"))
      (node (ref "U$1") (pin "A45") (pinfunction "A45_A45") (pintype "bidirectional"))
    )
    (net (code "66") (name "Net-(R46-PadP$2)") (class "Default")
      (node (ref "R46") (pin "P$2") (pinfunction "P$2_P$2") (pintype "passive"))
      (node (ref "U$1") (pin "A46") (pinfunction "A46_A46") (pintype "bidirectional"))
    )
    (net (code "67") (name "Net-(R47-PadP$2)") (class "Default")
      (node (ref "R47") (pin "P$2") (pinfunction "P$2_P$2") (pintype "passive"))
      (node (ref "U$1") (pin "A47") (pinfunction "A47_A47") (pintype "bidirectional"))
    )
    (net (code "68") (name "Net-(R48-PadP$2)") (class "Default")
      (node (ref "R48") (pin "P$2") (pinfunction "P$2_P$2") (pintype "passive"))
      (node (ref "U$1") (pin "A48") (pinfunction "A48_A48") (pintype "bidirectional"))
    )
    (net (code "69") (name "Net-(R49-PadP$2)") (class "Default")
      (node (ref "R49") (pin "P$2") (pinfunction "P$2_P$2") (pintype "passive"))
      (node (ref "U$1") (pin "A49") (pinfunction "A49_A49") (pintype "bidirectional"))
    )
    (net (code "70") (name "Net-(R50-PadP$2)") (class "Default")
      (node (ref "R50") (pin "P$2") (pinfunction "P$2_P$2") (pintype "passive"))
      (node (ref "U$1") (pin "A50") (pinfunction "A50_A50") (pintype "bidirectional"))
    )
    (net (code "71") (name "Net-(R51-PadP$2)") (class "Default")
      (node (ref "R51") (pin "P$2") (pinfunction "P$2_P$2") (pintype "passive"))
      (node (ref "U$1") (pin "A51") (pinfunction "A51_A51") (pintype "bidirectional"))
    )
    (net (code "72") (name "Net-(R52-PadP$2)") (class "Default")
      (node (ref "R52") (pin "P$2") (pinfunction "P$2_P$2") (pintype "passive"))
      (node (ref "U$1") (pin "A52") (pinfunction "A52_A52") (pintype "bidirectional"))
    )
    (net (code "73") (name "Net-(R53-PadP$2)") (class "Default")
      (node (ref "R53") (pin "P$2") (pinfunction "P$2_P$2") (pintype "passive"))
      (node (ref "U$1") (pin "A53") (pinfunction "A53_A53") (pintype "bidirectional"))
    )
    (net (code "74") (name "Net-(R54-PadP$2)") (class "Default")
      (node (ref "R54") (pin "P$2") (pinfunction "P$2_P$2") (pintype "passive"))
      (node (ref "U$1") (pin "A54") (pinfunction "A54_A54") (pintype "bidirectional"))
    )
    (net (code "75") (name "Net-(R55-PadP$2)") (class "Default")
      (node (ref "R55") (pin "P$2") (pinfunction "P$2_P$2") (pintype "passive"))
      (node (ref "U$1") (pin "A55") (pinfunction "A55_A55") (pintype "bidirectional"))
    )
    (net (code "76") (name "Net-(R56-PadP$2)") (class "Default")
      (node (ref "R56") (pin "P$2") (pinfunction "P$2_P$2") (pintype "passive"))
      (node (ref "U$1") (pin "A56") (pinfunction "A56_A56") (pintype "bidirectional"))
    )
    (net (code "77") (name "Net-(R57-PadP$2)") (class "Default")
      (node (ref "R57") (pin "P$2") (pinfunction "P$2_P$2") (pintype "passive"))
      (node (ref "U$1") (pin "A57") (pinfunction "A57_A57") (pintype "bidirectional"))
    )
    (net (code "78") (name "Net-(R58-PadP$2)") (class "Default")
      (node (ref "R58") (pin "P$2") (pinfunction "P$2_P$2") (pintype "passive"))
      (node (ref "U$1") (pin "A58") (pinfunction "A58_A58") (pintype "bidirectional"))
    )
    (net (code "79") (name "Net-(R59-PadP$2)") (class "Default")
      (node (ref "R59") (pin "P$2") (pinfunction "P$2_P$2") (pintype "passive"))
      (node (ref "U$1") (pin "A59") (pinfunction "A59_A59") (pintype "bidirectional"))
    )
    (net (code "80") (name "Net-(R60-PadP$2)") (class "Default")
      (node (ref "R60") (pin "P$2") (pinfunction "P$2_P$2") (pintype "passive"))
      (node (ref "U$1") (pin "A60") (pinfunction "A60_A60") (pintype "bidirectional"))
    )
    (net (code "81") (name "Net-(R61-PadP$2)") (class "Default")
      (node (ref "R61") (pin "P$2") (pinfunction "P$2_P$2") (pintype "passive"))
      (node (ref "U$1") (pin "A61") (pinfunction "A61_A61") (pintype "bidirectional"))
    )
    (net (code "82") (name "Net-(R62-PadP$2)") (class "Default")
      (node (ref "R62") (pin "P$2") (pinfunction "P$2_P$2") (pintype "passive"))
      (node (ref "U$1") (pin "A62") (pinfunction "A62_A62") (pintype "bidirectional"))
    )
    (net (code "83") (name "Net-(R63-PadP$2)") (class "Default")
      (node (ref "R63") (pin "P$2") (pinfunction "P$2_P$2") (pintype "passive"))
      (node (ref "U$1") (pin "A63") (pinfunction "A63_A63") (pintype "bidirectional"))
    )
    (net (code "84") (name "Net-(R64-PadP$2)") (class "Default")
      (node (ref "R64") (pin "P$2") (pinfunction "P$2_P$2") (pintype "passive"))
      (node (ref "U$1") (pin "A64") (pinfunction "A64_A64") (pintype "bidirectional"))
    )
    (net (code "85") (name "Net-(U$2-P1)") (class "Default")
      (node (ref "R64") (pin "P$1") (pinfunction "P$1_P$1") (pintype "passive"))
      (node (ref "U$2") (pin "41") (pinfunction "P1_41") (pintype "bidirectional"))
    )
    (net (code "86") (name "Net-(U$2-P2)") (class "Default")
      (node (ref "R63") (pin "P$1") (pinfunction "P$1_P$1") (pintype "passive"))
      (node (ref "U$2") (pin "42") (pinfunction "P2_42") (pintype "bidirectional"))
    )
    (net (code "87") (name "Net-(U$2-P3)") (class "Default")
      (node (ref "R62") (pin "P$1") (pinfunction "P$1_P$1") (pintype "passive"))
      (node (ref "U$2") (pin "43") (pinfunction "P3_43") (pintype "bidirectional"))
    )
    (net (code "88") (name "Net-(U$2-P4)") (class "Default")
      (node (ref "R61") (pin "P$1") (pinfunction "P$1_P$1") (pintype "passive"))
      (node (ref "U$2") (pin "44") (pinfunction "P4_44") (pintype "bidirectional"))
    )
    (net (code "89") (name "Net-(U$2-P5)") (class "Default")
      (node (ref "R60") (pin "P$1") (pinfunction "P$1_P$1") (pintype "passive"))
      (node (ref "U$2") (pin "45") (pinfunction "P5_45") (pintype "bidirectional"))
    )
    (net (code "90") (name "Net-(U$2-P6)") (class "Default")
      (node (ref "R59") (pin "P$1") (pinfunction "P$1_P$1") (pintype "passive"))
      (node (ref "U$2") (pin "46") (pinfunction "P6_46") (pintype "bidirectional"))
    )
    (net (code "91") (name "Net-(U$2-P7)") (class "Default")
      (node (ref "R58") (pin "P$1") (pinfunction "P$1_P$1") (pintype "passive"))
      (node (ref "U$2") (pin "47") (pinfunction "P7_47") (pintype "bidirectional"))
    )
    (net (code "92") (name "Net-(U$2-P8)") (class "Default")
      (node (ref "R57") (pin "P$1") (pinfunction "P$1_P$1") (pintype "passive"))
      (node (ref "U$2") (pin "48") (pinfunction "P8_48") (pintype "bidirectional"))
    )
    (net (code "93") (name "Net-(U$2-P9)") (class "Default")
      (node (ref "R56") (pin "P$1") (pinfunction "P$1_P$1") (pintype "passive"))
      (node (ref "U$2") (pin "49") (pinfunction "P9_49") (pintype "bidirectional"))
    )
    (net (code "94") (name "Net-(U$2-P10)") (class "Default")
      (node (ref "R55") (pin "P$1") (pinfunction "P$1_P$1") (pintype "passive"))
      (node (ref "U$2") (pin "50") (pinfunction "P10_50") (pintype "bidirectional"))
    )
    (net (code "95") (name "Net-(U$2-P11)") (class "Default")
      (node (ref "R54") (pin "P$1") (pinfunction "P$1_P$1") (pintype "passive"))
      (node (ref "U$2") (pin "51") (pinfunction "P11_51") (pintype "bidirectional"))
    )
    (net (code "96") (name "Net-(U$2-P12)") (class "Default")
      (node (ref "R53") (pin "P$1") (pinfunction "P$1_P$1") (pintype "passive"))
      (node (ref "U$2") (pin "52") (pinfunction "P12_52") (pintype "bidirectional"))
    )
    (net (code "97") (name "Net-(U$2-P13)") (class "Default")
      (node (ref "R52") (pin "P$1") (pinfunction "P$1_P$1") (pintype "passive"))
      (node (ref "U$2") (pin "53") (pinfunction "P13_53") (pintype "bidirectional"))
    )
    (net (code "98") (name "Net-(U$2-P14)") (class "Default")
      (node (ref "R51") (pin "P$1") (pinfunction "P$1_P$1") (pintype "passive"))
      (node (ref "U$2") (pin "54") (pinfunction "P14_54") (pintype "bidirectional"))
    )
    (net (code "99") (name "Net-(U$2-P15)") (class "Default")
      (node (ref "R50") (pin "P$1") (pinfunction "P$1_P$1") (pintype "passive"))
      (node (ref "U$2") (pin "55") (pinfunction "P15_55") (pintype "bidirectional"))
    )
    (net (code "100") (name "Net-(U$2-P16)") (class "Default")
      (node (ref "R49") (pin "P$1") (pinfunction "P$1_P$1") (pintype "passive"))
      (node (ref "U$2") (pin "56") (pinfunction "P16_56") (pintype "bidirectional"))
    )
    (net (code "101") (name "Net-(U$2-P17)") (class "Default")
      (node (ref "R48") (pin "P$1") (pinfunction "P$1_P$1") (pintype "passive"))
      (node (ref "U$2") (pin "57") (pinfunction "P17_57") (pintype "bidirectional"))
    )
    (net (code "102") (name "Net-(U$2-P18)") (class "Default")
      (node (ref "R47") (pin "P$1") (pinfunction "P$1_P$1") (pintype "passive"))
      (node (ref "U$2") (pin "58") (pinfunction "P18_58") (pintype "bidirectional"))
    )
    (net (code "103") (name "Net-(U$2-P19)") (class "Default")
      (node (ref "R46") (pin "P$1") (pinfunction "P$1_P$1") (pintype "passive"))
      (node (ref "U$2") (pin "59") (pinfunction "P19_59") (pintype "bidirectional"))
    )
    (net (code "104") (name "Net-(U$2-P20)") (class "Default")
      (node (ref "R45") (pin "P$1") (pinfunction "P$1_P$1") (pintype "passive"))
      (node (ref "U$2") (pin "60") (pinfunction "P20_60") (pintype "bidirectional"))
    )
    (net (code "105") (name "Net-(U$2-P21)") (class "Default")
      (node (ref "R44") (pin "P$1") (pinfunction "P$1_P$1") (pintype "passive"))
      (node (ref "U$2") (pin "61") (pinfunction "P21_61") (pintype "bidirectional"))
    )
    (net (code "106") (name "Net-(U$2-P22)") (class "Default")
      (node (ref "R43") (pin "P$1") (pinfunction "P$1_P$1") (pintype "passive"))
      (node (ref "U$2") (pin "62") (pinfunction "P22_62") (pintype "bidirectional"))
    )
    (net (code "107") (name "Net-(U$2-P23)") (class "Default")
      (node (ref "R42") (pin "P$1") (pinfunction "P$1_P$1") (pintype "passive"))
      (node (ref "U$2") (pin "63") (pinfunction "P23_63") (pintype "bidirectional"))
    )
    (net (code "108") (name "Net-(U$2-P24)") (class "Default")
      (node (ref "R41") (pin "P$1") (pinfunction "P$1_P$1") (pintype "passive"))
      (node (ref "U$2") (pin "64") (pinfunction "P24_64") (pintype "bidirectional"))
    )
    (net (code "109") (name "Net-(U$2-P25)") (class "Default")
      (node (ref "R40") (pin "P$1") (pinfunction "P$1_P$1") (pintype "passive"))
      (node (ref "U$2") (pin "65") (pinfunction "P25_65") (pintype "bidirectional"))
    )
    (net (code "110") (name "Net-(U$2-P26)") (class "Default")
      (node (ref "R39") (pin "P$1") (pinfunction "P$1_P$1") (pintype "passive"))
      (node (ref "U$2") (pin "66") (pinfunction "P26_66") (pintype "bidirectional"))
    )
    (net (code "111") (name "Net-(U$2-P27)") (class "Default")
      (node (ref "R38") (pin "P$1") (pinfunction "P$1_P$1") (pintype "passive"))
      (node (ref "U$2") (pin "67") (pinfunction "P27_67") (pintype "bidirectional"))
    )
    (net (code "112") (name "Net-(U$2-P28)") (class "Default")
      (node (ref "R37") (pin "P$1") (pinfunction "P$1_P$1") (pintype "passive"))
      (node (ref "U$2") (pin "68") (pinfunction "P28_68") (pintype "bidirectional"))
    )
    (net (code "113") (name "Net-(U$2-P29)") (class "Default")
      (node (ref "R36") (pin "P$1") (pinfunction "P$1_P$1") (pintype "passive"))
      (node (ref "U$2") (pin "69") (pinfunction "P29_69") (pintype "bidirectional"))
    )
    (net (code "114") (name "Net-(U$2-P30)") (class "Default")
      (node (ref "R35") (pin "P$1") (pinfunction "P$1_P$1") (pintype "passive"))
      (node (ref "U$2") (pin "70") (pinfunction "P30_70") (pintype "bidirectional"))
    )
    (net (code "115") (name "Net-(U$2-P31)") (class "Default")
      (node (ref "R34") (pin "P$1") (pinfunction "P$1_P$1") (pintype "passive"))
      (node (ref "U$2") (pin "71") (pinfunction "P31_71") (pintype "bidirectional"))
    )
    (net (code "116") (name "Net-(U$2-P32)") (class "Default")
      (node (ref "R33") (pin "P$1") (pinfunction "P$1_P$1") (pintype "passive"))
      (node (ref "U$2") (pin "72") (pinfunction "P32_72") (pintype "bidirectional"))
    )
    (net (code "117") (name "Net-(U$2-P33)") (class "Default")
      (node (ref "R32") (pin "P$1") (pinfunction "P$1_P$1") (pintype "passive"))
      (node (ref "U$2") (pin "73") (pinfunction "P33_73") (pintype "bidirectional"))
    )
    (net (code "118") (name "Net-(U$2-P34)") (class "Default")
      (node (ref "R31") (pin "P$1") (pinfunction "P$1_P$1") (pintype "passive"))
      (node (ref "U$2") (pin "74") (pinfunction "P34_74") (pintype "bidirectional"))
    )
    (net (code "119") (name "Net-(U$2-P35)") (class "Default")
      (node (ref "R30") (pin "P$1") (pinfunction "P$1_P$1") (pintype "passive"))
      (node (ref "U$2") (pin "75") (pinfunction "P35_75") (pintype "bidirectional"))
    )
    (net (code "120") (name "Net-(U$2-P36)") (class "Default")
      (node (ref "R29") (pin "P$1") (pinfunction "P$1_P$1") (pintype "passive"))
      (node (ref "U$2") (pin "76") (pinfunction "P36_76") (pintype "bidirectional"))
    )
    (net (code "121") (name "Net-(U$2-P37)") (class "Default")
      (node (ref "R28") (pin "P$1") (pinfunction "P$1_P$1") (pintype "passive"))
      (node (ref "U$2") (pin "77") (pinfunction "P37_77") (pintype "bidirectional"))
    )
    (net (code "122") (name "Net-(U$2-P38)") (class "Default")
      (node (ref "R27") (pin "P$1") (pinfunction "P$1_P$1") (pintype "passive"))
      (node (ref "U$2") (pin "78") (pinfunction "P38_78") (pintype "bidirectional"))
    )
    (net (code "123") (name "Net-(U$2-P39)") (class "Default")
      (node (ref "R26") (pin "P$1") (pinfunction "P$1_P$1") (pintype "passive"))
      (node (ref "U$2") (pin "79") (pinfunction "P39_79") (pintype "bidirectional"))
    )
    (net (code "124") (name "Net-(U$2-P40)") (class "Default")
      (node (ref "R25") (pin "P$1") (pinfunction "P$1_P$1") (pintype "passive"))
      (node (ref "U$2") (pin "80") (pinfunction "P40_80") (pintype "bidirectional"))
    )
    (net (code "125") (name "Net-(U$2-P41)") (class "Default")
      (node (ref "R24") (pin "P$1") (pinfunction "P$1_P$1") (pintype "passive"))
      (node (ref "U$2") (pin "1") (pinfunction "P41_1") (pintype "bidirectional"))
    )
    (net (code "126") (name "Net-(U$2-P42)") (class "Default")
      (node (ref "R23") (pin "P$1") (pinfunction "P$1_P$1") (pintype "passive"))
      (node (ref "U$2") (pin "2") (pinfunction "P42_2") (pintype "bidirectional"))
    )
    (net (code "127") (name "Net-(U$2-P43)") (class "Default")
      (node (ref "R22") (pin "P$1") (pinfunction "P$1_P$1") (pintype "passive"))
      (node (ref "U$2") (pin "3") (pinfunction "P43_3") (pintype "bidirectional"))
    )
    (net (code "128") (name "Net-(U$2-P44)") (class "Default")
      (node (ref "R21") (pin "P$1") (pinfunction "P$1_P$1") (pintype "passive"))
      (node (ref "U$2") (pin "4") (pinfunction "P44_4") (pintype "bidirectional"))
    )
    (net (code "129") (name "Net-(U$2-P45)") (class "Default")
      (node (ref "R20") (pin "P$1") (pinfunction "P$1_P$1") (pintype "passive"))
      (node (ref "U$2") (pin "5") (pinfunction "P45_5") (pintype "bidirectional"))
    )
    (net (code "130") (name "Net-(U$2-P46)") (class "Default")
      (node (ref "R19") (pin "P$1") (pinfunction "P$1_P$1") (pintype "passive"))
      (node (ref "U$2") (pin "6") (pinfunction "P46_6") (pintype "bidirectional"))
    )
    (net (code "131") (name "Net-(U$2-P47)") (class "Default")
      (node (ref "R18") (pin "P$1") (pinfunction "P$1_P$1") (pintype "passive"))
      (node (ref "U$2") (pin "7") (pinfunction "P47_7") (pintype "bidirectional"))
    )
    (net (code "132") (name "Net-(U$2-P48)") (class "Default")
      (node (ref "R17") (pin "P$1") (pinfunction "P$1_P$1") (pintype "passive"))
      (node (ref "U$2") (pin "8") (pinfunction "P48_8") (pintype "bidirectional"))
    )
    (net (code "133") (name "Net-(U$2-P49)") (class "Default")
      (node (ref "R16") (pin "P$1") (pinfunction "P$1_P$1") (pintype "passive"))
      (node (ref "U$2") (pin "9") (pinfunction "P49_9") (pintype "bidirectional"))
    )
    (net (code "134") (name "Net-(U$2-P50)") (class "Default")
      (node (ref "R15") (pin "P$1") (pinfunction "P$1_P$1") (pintype "passive"))
      (node (ref "U$2") (pin "10") (pinfunction "P50_10") (pintype "bidirectional"))
    )
    (net (code "135") (name "Net-(U$2-P51)") (class "Default")
      (node (ref "R14") (pin "P$1") (pinfunction "P$1_P$1") (pintype "passive"))
      (node (ref "U$2") (pin "11") (pinfunction "P51_11") (pintype "bidirectional"))
    )
    (net (code "136") (name "Net-(U$2-P52)") (class "Default")
      (node (ref "R13") (pin "P$1") (pinfunction "P$1_P$1") (pintype "passive"))
      (node (ref "U$2") (pin "12") (pinfunction "P52_12") (pintype "bidirectional"))
    )
    (net (code "137") (name "Net-(U$2-P53)") (class "Default")
      (node (ref "R12") (pin "P$1") (pinfunction "P$1_P$1") (pintype "passive"))
      (node (ref "U$2") (pin "13") (pinfunction "P53_13") (pintype "bidirectional"))
    )
    (net (code "138") (name "Net-(U$2-P54)") (class "Default")
      (node (ref "R11") (pin "P$1") (pinfunction "P$1_P$1") (pintype "passive"))
      (node (ref "U$2") (pin "14") (pinfunction "P54_14") (pintype "bidirectional"))
    )
    (net (code "139") (name "Net-(U$2-P55)") (class "Default")
      (node (ref "R10") (pin "P$1") (pinfunction "P$1_P$1") (pintype "passive"))
      (node (ref "U$2") (pin "15") (pinfunction "P55_15") (pintype "bidirectional"))
    )
    (net (code "140") (name "Net-(U$2-P56)") (class "Default")
      (node (ref "R9") (pin "P$1") (pinfunction "P$1_P$1") (pintype "passive"))
      (node (ref "U$2") (pin "16") (pinfunction "P56_16") (pintype "bidirectional"))
    )
    (net (code "141") (name "Net-(U$2-P57)") (class "Default")
      (node (ref "R8") (pin "P$1") (pinfunction "P$1_P$1") (pintype "passive"))
      (node (ref "U$2") (pin "17") (pinfunction "P57_17") (pintype "bidirectional"))
    )
    (net (code "142") (name "Net-(U$2-P58)") (class "Default")
      (node (ref "R7") (pin "P$1") (pinfunction "P$1_P$1") (pintype "passive"))
      (node (ref "U$2") (pin "18") (pinfunction "P58_18") (pintype "bidirectional"))
    )
    (net (code "143") (name "Net-(U$2-P59)") (class "Default")
      (node (ref "R6") (pin "P$1") (pinfunction "P$1_P$1") (pintype "passive"))
      (node (ref "U$2") (pin "19") (pinfunction "P59_19") (pintype "bidirectional"))
    )
    (net (code "144") (name "Net-(U$2-P60)") (class "Default")
      (node (ref "R5") (pin "P$1") (pinfunction "P$1_P$1") (pintype "passive"))
      (node (ref "U$2") (pin "20") (pinfunction "P60_20") (pintype "bidirectional"))
    )
    (net (code "145") (name "Net-(U$2-P61)") (class "Default")
      (node (ref "R4") (pin "P$1") (pinfunction "P$1_P$1") (pintype "passive"))
      (node (ref "U$2") (pin "21") (pinfunction "P61_21") (pintype "bidirectional"))
    )
    (net (code "146") (name "Net-(U$2-P62)") (class "Default")
      (node (ref "R3") (pin "P$1") (pinfunction "P$1_P$1") (pintype "passive"))
      (node (ref "U$2") (pin "22") (pinfunction "P62_22") (pintype "bidirectional"))
    )
    (net (code "147") (name "Net-(U$2-P63)") (class "Default")
      (node (ref "R2") (pin "P$1") (pinfunction "P$1_P$1") (pintype "passive"))
      (node (ref "U$2") (pin "23") (pinfunction "P63_23") (pintype "bidirectional"))
    )
    (net (code "148") (name "Net-(U$2-P64)") (class "Default")
      (node (ref "R1") (pin "P$1") (pinfunction "P$1_P$1") (pintype "passive"))
      (node (ref "U$2") (pin "24") (pinfunction "P64_24") (pintype "bidirectional"))
    )
    (net (code "149") (name "Net-(U$3-DATAIN)") (class "Default")
      (node (ref "U$3") (pin "32") (pinfunction "DATAIN_32") (pintype "bidirectional"))
      (node (ref "U$4") (pin "23") (pinfunction "DATAOUT_23") (pintype "bidirectional"))
    )
    (net (code "150") (name "Net-(U$3-P1)") (class "Default")
      (node (ref "U$1") (pin "K1") (pinfunction "K1_K1") (pintype "bidirectional"))
      (node (ref "U$3") (pin "35") (pinfunction "P1_35") (pintype "bidirectional"))
    )
    (net (code "151") (name "Net-(U$3-P2)") (class "Default")
      (node (ref "U$1") (pin "K2") (pinfunction "K2_K2") (pintype "bidirectional"))
      (node (ref "U$3") (pin "36") (pinfunction "P2_36") (pintype "bidirectional"))
    )
    (net (code "152") (name "Net-(U$3-P3)") (class "Default")
      (node (ref "U$1") (pin "K3") (pinfunction "K3_K3") (pintype "bidirectional"))
      (node (ref "U$3") (pin "37") (pinfunction "P3_37") (pintype "bidirectional"))
    )
    (net (code "153") (name "Net-(U$3-P4)") (class "Default")
      (node (ref "U$1") (pin "K4") (pinfunction "K4_K4") (pintype "bidirectional"))
      (node (ref "U$3") (pin "38") (pinfunction "P4_38") (pintype "bidirectional"))
    )
    (net (code "154") (name "Net-(U$3-P5)") (class "Default")
      (node (ref "U$1") (pin "K5") (pinfunction "K5_K5") (pintype "bidirectional"))
      (node (ref "U$3") (pin "39") (pinfunction "P5_39") (pintype "bidirectional"))
    )
    (net (code "155") (name "Net-(U$3-P6)") (class "Default")
      (node (ref "U$1") (pin "K6") (pinfunction "K6_K6") (pintype "bidirectional"))
      (node (ref "U$3") (pin "40") (pinfunction "P6_40") (pintype "bidirectional"))
    )
    (net (code "156") (name "Net-(U$3-P7)") (class "Default")
      (node (ref "U$1") (pin "K7") (pinfunction "K7_K7") (pintype "bidirectional"))
      (node (ref "U$3") (pin "41") (pinfunction "P7_41") (pintype "bidirectional"))
    )
    (net (code "157") (name "Net-(U$3-P8)") (class "Default")
      (node (ref "U$1") (pin "K8") (pinfunction "K8_K8") (pintype "bidirectional"))
      (node (ref "U$3") (pin "42") (pinfunction "P8_42") (pintype "bidirectional"))
    )
    (net (code "158") (name "Net-(U$3-P9)") (class "Default")
      (node (ref "U$1") (pin "K9") (pinfunction "K9_K9") (pintype "bidirectional"))
      (node (ref "U$3") (pin "43") (pinfunction "P9_43") (pintype "bidirectional"))
    )
    (net (code "159") (name "Net-(U$3-P10)") (class "Default")
      (node (ref "U$1") (pin "K10") (pinfunction "K10_K10") (pintype "bidirectional"))
      (node (ref "U$3") (pin "44") (pinfunction "P10_44") (pintype "bidirectional"))
    )
    (net (code "160") (name "Net-(U$3-P11)") (class "Default")
      (node (ref "U$1") (pin "K11") (pinfunction "K11_K11") (pintype "bidirectional"))
      (node (ref "U$3") (pin "1") (pinfunction "P11_1") (pintype "bidirectional"))
    )
    (net (code "161") (name "Net-(U$3-P12)") (class "Default")
      (node (ref "U$1") (pin "K12") (pinfunction "K12_K12") (pintype "bidirectional"))
      (node (ref "U$3") (pin "2") (pinfunction "P12_2") (pintype "bidirectional"))
    )
    (net (code "162") (name "Net-(U$3-P13)") (class "Default")
      (node (ref "U$1") (pin "K13") (pinfunction "K13_K13") (pintype "bidirectional"))
      (node (ref "U$3") (pin "3") (pinfunction "P13_3") (pintype "bidirectional"))
    )
    (net (code "163") (name "Net-(U$3-P14)") (class "Default")
      (node (ref "U$1") (pin "K14") (pinfunction "K14_K14") (pintype "bidirectional"))
      (node (ref "U$3") (pin "4") (pinfunction "P14_4") (pintype "bidirectional"))
    )
    (net (code "164") (name "Net-(U$3-P15)") (class "Default")
      (node (ref "U$1") (pin "K15") (pinfunction "K15_K15") (pintype "bidirectional"))
      (node (ref "U$3") (pin "5") (pinfunction "P15_5") (pintype "bidirectional"))
    )
    (net (code "165") (name "Net-(U$3-P16)") (class "Default")
      (node (ref "U$1") (pin "K16") (pinfunction "K16_K16") (pintype "bidirectional"))
      (node (ref "U$3") (pin "6") (pinfunction "P16_6") (pintype "bidirectional"))
    )
    (net (code "166") (name "Net-(U$3-P17)") (class "Default")
      (node (ref "U$1") (pin "K17") (pinfunction "K17_K17") (pintype "bidirectional"))
      (node (ref "U$3") (pin "7") (pinfunction "P17_7") (pintype "bidirectional"))
    )
    (net (code "167") (name "Net-(U$3-P18)") (class "Default")
      (node (ref "U$1") (pin "K18") (pinfunction "K18_K18") (pintype "bidirectional"))
      (node (ref "U$3") (pin "8") (pinfunction "P18_8") (pintype "bidirectional"))
    )
    (net (code "168") (name "Net-(U$3-P19)") (class "Default")
      (node (ref "U$1") (pin "K19") (pinfunction "K19_K19") (pintype "bidirectional"))
      (node (ref "U$3") (pin "9") (pinfunction "P19_9") (pintype "bidirectional"))
    )
    (net (code "169") (name "Net-(U$3-P20)") (class "Default")
      (node (ref "U$1") (pin "K20") (pinfunction "K20_K20") (pintype "bidirectional"))
      (node (ref "U$3") (pin "10") (pinfunction "P20_10") (pintype "bidirectional"))
    )
    (net (code "170") (name "Net-(U$3-P21)") (class "Default")
      (node (ref "U$1") (pin "K21") (pinfunction "K21_K21") (pintype "bidirectional"))
      (node (ref "U$3") (pin "11") (pinfunction "P21_11") (pintype "bidirectional"))
    )
    (net (code "171") (name "Net-(U$3-P22)") (class "Default")
      (node (ref "U$1") (pin "K22") (pinfunction "K22_K22") (pintype "bidirectional"))
      (node (ref "U$3") (pin "12") (pinfunction "P22_12") (pintype "bidirectional"))
    )
    (net (code "172") (name "Net-(U$3-P23)") (class "Default")
      (node (ref "U$1") (pin "K23") (pinfunction "K23_K23") (pintype "bidirectional"))
      (node (ref "U$3") (pin "13") (pinfunction "P23_13") (pintype "bidirectional"))
    )
    (net (code "173") (name "Net-(U$3-P24)") (class "Default")
      (node (ref "U$1") (pin "K24") (pinfunction "K24_K24") (pintype "bidirectional"))
      (node (ref "U$3") (pin "14") (pinfunction "P24_14") (pintype "bidirectional"))
    )
    (net (code "174") (name "Net-(U$3-P25)") (class "Default")
      (node (ref "U$1") (pin "K25") (pinfunction "K25_K25") (pintype "bidirectional"))
      (node (ref "U$3") (pin "15") (pinfunction "P25_15") (pintype "bidirectional"))
    )
    (net (code "175") (name "Net-(U$3-P26)") (class "Default")
      (node (ref "U$1") (pin "K26") (pinfunction "K26_K26") (pintype "bidirectional"))
      (node (ref "U$3") (pin "16") (pinfunction "P26_16") (pintype "bidirectional"))
    )
    (net (code "176") (name "Net-(U$3-P27)") (class "Default")
      (node (ref "U$1") (pin "K27") (pinfunction "K27_K27") (pintype "bidirectional"))
      (node (ref "U$3") (pin "17") (pinfunction "P27_17") (pintype "bidirectional"))
    )
    (net (code "177") (name "Net-(U$3-P28)") (class "Default")
      (node (ref "U$1") (pin "K28") (pinfunction "K28_K28") (pintype "bidirectional"))
      (node (ref "U$3") (pin "18") (pinfunction "P28_18") (pintype "bidirectional"))
    )
    (net (code "178") (name "Net-(U$3-P29)") (class "Default")
      (node (ref "U$1") (pin "K29") (pinfunction "K29_K29") (pintype "bidirectional"))
      (node (ref "U$3") (pin "19") (pinfunction "P29_19") (pintype "bidirectional"))
    )
    (net (code "179") (name "Net-(U$3-P30)") (class "Default")
      (node (ref "U$1") (pin "K30") (pinfunction "K30_K30") (pintype "bidirectional"))
      (node (ref "U$3") (pin "20") (pinfunction "P30_20") (pintype "bidirectional"))
    )
    (net (code "180") (name "Net-(U$3-P31)") (class "Default")
      (node (ref "U$1") (pin "K31") (pinfunction "K31_K31") (pintype "bidirectional"))
      (node (ref "U$3") (pin "21") (pinfunction "P31_21") (pintype "bidirectional"))
    )
    (net (code "181") (name "Net-(U$3-P32)") (class "Default")
      (node (ref "U$1") (pin "K32") (pinfunction "K32_K32") (pintype "bidirectional"))
      (node (ref "U$3") (pin "22") (pinfunction "P32_22") (pintype "bidirectional"))
    )
    (net (code "182") (name "Net-(U$4-P1)") (class "Default")
      (node (ref "U$1") (pin "K33") (pinfunction "K33_K33") (pintype "bidirectional"))
      (node (ref "U$4") (pin "35") (pinfunction "P1_35") (pintype "bidirectional"))
    )
    (net (code "183") (name "Net-(U$4-P2)") (class "Default")
      (node (ref "U$1") (pin "K34") (pinfunction "K34_K34") (pintype "bidirectional"))
      (node (ref "U$4") (pin "36") (pinfunction "P2_36") (pintype "bidirectional"))
    )
    (net (code "184") (name "Net-(U$4-P3)") (class "Default")
      (node (ref "U$1") (pin "K35") (pinfunction "K35_K35") (pintype "bidirectional"))
      (node (ref "U$4") (pin "37") (pinfunction "P3_37") (pintype "bidirectional"))
    )
    (net (code "185") (name "Net-(U$4-P4)") (class "Default")
      (node (ref "U$1") (pin "K36") (pinfunction "K36_K36") (pintype "bidirectional"))
      (node (ref "U$4") (pin "38") (pinfunction "P4_38") (pintype "bidirectional"))
    )
    (net (code "186") (name "Net-(U$4-P5)") (class "Default")
      (node (ref "U$1") (pin "K37") (pinfunction "K37_K37") (pintype "bidirectional"))
      (node (ref "U$4") (pin "39") (pinfunction "P5_39") (pintype "bidirectional"))
    )
    (net (code "187") (name "Net-(U$4-P6)") (class "Default")
      (node (ref "U$1") (pin "K38") (pinfunction "K38_K38") (pintype "bidirectional"))
      (node (ref "U$4") (pin "40") (pinfunction "P6_40") (pintype "bidirectional"))
    )
    (net (code "188") (name "Net-(U$4-P7)") (class "Default")
      (node (ref "U$1") (pin "K39") (pinfunction "K39_K39") (pintype "bidirectional"))
      (node (ref "U$4") (pin "41") (pinfunction "P7_41") (pintype "bidirectional"))
    )
    (net (code "189") (name "Net-(U$4-P8)") (class "Default")
      (node (ref "U$1") (pin "K40") (pinfunction "K40_K40") (pintype "bidirectional"))
      (node (ref "U$4") (pin "42") (pinfunction "P8_42") (pintype "bidirectional"))
    )
    (net (code "190") (name "Net-(U$4-P9)") (class "Default")
      (node (ref "U$1") (pin "K41") (pinfunction "K41_K41") (pintype "bidirectional"))
      (node (ref "U$4") (pin "43") (pinfunction "P9_43") (pintype "bidirectional"))
    )
    (net (code "191") (name "Net-(U$4-P10)") (class "Default")
      (node (ref "U$1") (pin "K42") (pinfunction "K42_K42") (pintype "bidirectional"))
      (node (ref "U$4") (pin "44") (pinfunction "P10_44") (pintype "bidirectional"))
    )
    (net (code "192") (name "Net-(U$4-P11)") (class "Default")
      (node (ref "U$1") (pin "K43") (pinfunction "K43_K43") (pintype "bidirectional"))
      (node (ref "U$4") (pin "1") (pinfunction "P11_1") (pintype "bidirectional"))
    )
    (net (code "193") (name "Net-(U$4-P12)") (class "Default")
      (node (ref "U$1") (pin "K44") (pinfunction "K44_K44") (pintype "bidirectional"))
      (node (ref "U$4") (pin "2") (pinfunction "P12_2") (pintype "bidirectional"))
    )
    (net (code "194") (name "Net-(U$4-P13)") (class "Default")
      (node (ref "U$1") (pin "K45") (pinfunction "K45_K45") (pintype "bidirectional"))
      (node (ref "U$4") (pin "3") (pinfunction "P13_3") (pintype "bidirectional"))
    )
    (net (code "195") (name "Net-(U$4-P14)") (class "Default")
      (node (ref "U$1") (pin "K46") (pinfunction "K46_K46") (pintype "bidirectional"))
      (node (ref "U$4") (pin "4") (pinfunction "P14_4") (pintype "bidirectional"))
    )
    (net (code "196") (name "Net-(U$4-P15)") (class "Default")
      (node (ref "U$1") (pin "K47") (pinfunction "K47_K47") (pintype "bidirectional"))
      (node (ref "U$4") (pin "5") (pinfunction "P15_5") (pintype "bidirectional"))
    )
    (net (code "197") (name "Net-(U$4-P16)") (class "Default")
      (node (ref "U$1") (pin "K48") (pinfunction "K48_K48") (pintype "bidirectional"))
      (node (ref "U$4") (pin "6") (pinfunction "P16_6") (pintype "bidirectional"))
    )
    (net (code "198") (name "Net-(U$4-P17)") (class "Default")
      (node (ref "U$1") (pin "K49") (pinfunction "K49_K49") (pintype "bidirectional"))
      (node (ref "U$4") (pin "7") (pinfunction "P17_7") (pintype "bidirectional"))
    )
    (net (code "199") (name "Net-(U$4-P18)") (class "Default")
      (node (ref "U$1") (pin "K50") (pinfunction "K50_K50") (pintype "bidirectional"))
      (node (ref "U$4") (pin "8") (pinfunction "P18_8") (pintype "bidirectional"))
    )
    (net (code "200") (name "Net-(U$4-P19)") (class "Default")
      (node (ref "U$1") (pin "K51") (pinfunction "K51_K51") (pintype "bidirectional"))
      (node (ref "U$4") (pin "9") (pinfunction "P19_9") (pintype "bidirectional"))
    )
    (net (code "201") (name "Net-(U$4-P20)") (class "Default")
      (node (ref "U$1") (pin "K52") (pinfunction "K52_K52") (pintype "bidirectional"))
      (node (ref "U$4") (pin "10") (pinfunction "P20_10") (pintype "bidirectional"))
    )
    (net (code "202") (name "Net-(U$4-P21)") (class "Default")
      (node (ref "U$1") (pin "K53") (pinfunction "K53_K53") (pintype "bidirectional"))
      (node (ref "U$4") (pin "11") (pinfunction "P21_11") (pintype "bidirectional"))
    )
    (net (code "203") (name "Net-(U$4-P22)") (class "Default")
      (node (ref "U$1") (pin "K54") (pinfunction "K54_K54") (pintype "bidirectional"))
      (node (ref "U$4") (pin "12") (pinfunction "P22_12") (pintype "bidirectional"))
    )
    (net (code "204") (name "Net-(U$4-P23)") (class "Default")
      (node (ref "U$1") (pin "K55") (pinfunction "K55_K55") (pintype "bidirectional"))
      (node (ref "U$4") (pin "13") (pinfunction "P23_13") (pintype "bidirectional"))
    )
    (net (code "205") (name "Net-(U$4-P24)") (class "Default")
      (node (ref "U$1") (pin "K56") (pinfunction "K56_K56") (pintype "bidirectional"))
      (node (ref "U$4") (pin "14") (pinfunction "P24_14") (pintype "bidirectional"))
    )
    (net (code "206") (name "Net-(U$4-P25)") (class "Default")
      (node (ref "U$1") (pin "K57") (pinfunction "K57_K57") (pintype "bidirectional"))
      (node (ref "U$4") (pin "15") (pinfunction "P25_15") (pintype "bidirectional"))
    )
    (net (code "207") (name "Net-(U$4-P26)") (class "Default")
      (node (ref "U$1") (pin "K58") (pinfunction "K58_K58") (pintype "bidirectional"))
      (node (ref "U$4") (pin "16") (pinfunction "P26_16") (pintype "bidirectional"))
    )
    (net (code "208") (name "Net-(U$4-P27)") (class "Default")
      (node (ref "U$1") (pin "K59") (pinfunction "K59_K59") (pintype "bidirectional"))
      (node (ref "U$4") (pin "17") (pinfunction "P27_17") (pintype "bidirectional"))
    )
    (net (code "209") (name "Net-(U$4-P28)") (class "Default")
      (node (ref "U$1") (pin "K60") (pinfunction "K60_K60") (pintype "bidirectional"))
      (node (ref "U$4") (pin "18") (pinfunction "P28_18") (pintype "bidirectional"))
    )
    (net (code "210") (name "Net-(U$4-P29)") (class "Default")
      (node (ref "U$1") (pin "K61") (pinfunction "K61_K61") (pintype "bidirectional"))
      (node (ref "U$4") (pin "19") (pinfunction "P29_19") (pintype "bidirectional"))
    )
    (net (code "211") (name "Net-(U$4-P30)") (class "Default")
      (node (ref "U$1") (pin "K62") (pinfunction "K62_K62") (pintype "bidirectional"))
      (node (ref "U$4") (pin "20") (pinfunction "P30_20") (pintype "bidirectional"))
    )
    (net (code "212") (name "Net-(U$4-P31)") (class "Default")
      (node (ref "U$1") (pin "K63") (pinfunction "K63_K63") (pintype "bidirectional"))
      (node (ref "U$4") (pin "21") (pinfunction "P31_21") (pintype "bidirectional"))
    )
    (net (code "213") (name "Net-(U$4-P32)") (class "Default")
      (node (ref "U$1") (pin "K64") (pinfunction "K64_K64") (pintype "bidirectional"))
      (node (ref "U$4") (pin "22") (pinfunction "P32_22") (pintype "bidirectional"))
    )
    (net (code "214") (name "unconnected-(IC1F-I-Pad14)") (class "Default")
      (node (ref "IC1") (pin "14") (pinfunction "I_14") (pintype "input"))
    )
    (net (code "215") (name "unconnected-(IC1F-O-Pad15)") (class "Default")
      (node (ref "IC1") (pin "15") (pinfunction "O_15") (pintype "output"))
    )
    (net (code "216") (name "unconnected-(IC2F-I-Pad14)") (class "Default")
      (node (ref "IC2") (pin "14") (pinfunction "I_14") (pintype "input"))
    )
    (net (code "217") (name "unconnected-(IC2F-O-Pad15)") (class "Default")
      (node (ref "IC2") (pin "15") (pinfunction "O_15") (pintype "output"))
    )
    (net (code "218") (name "unconnected-(U$2-DATAOUT-Pad39)") (class "Default")
      (node (ref "U$2") (pin "39") (pinfunction "DATAOUT_39") (pintype "bidirectional"))
    )
    (net (code "219") (name "unconnected-(U$3-DATAOUT-Pad23)") (class "Default")
      (node (ref "U$3") (pin "23") (pinfunction "DATAOUT_23") (pintype "bidirectional"))
    )
  )
)
